# WT901.net
KiCad netlist of a schematic drawn in EAGLE
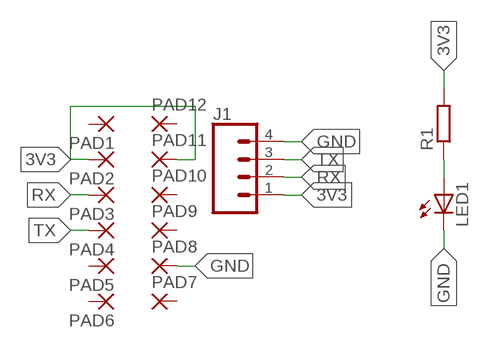
[diagram p0: schematic, sheet 1]

(export (version "E")
  (design (tool "Eeschema 10.0.6"))
  (components
    (comp (ref "J1")
      (value "CONN_04JST-SMD")
      (footprint "eagle-import:JST-4-SMD")
      (libsource (lib "eagle-import") (part "CONN_04JST-SMD"))
    )
    (comp (ref "LED1")
      (value "LEDCHIPLED_0805")
      (footprint "eagle-import:CHIPLED_0805")
      (libsource (lib "eagle-import") (part "LEDCHIPLED_0805"))
    )
    (comp (ref "PAD1")
      (value "SMD2")
      (footprint "eagle-import:SMD1,27-2,54")
      (libsource (lib "eagle-import") (part "SMD2"))
    )
    (comp (ref "PAD2")
      (value "SMD2")
      (footprint "eagle-import:SMD1,27-2,54")
      (libsource (lib "eagle-import") (part "SMD2"))
    )
    (comp (ref "PAD3")
      (value "SMD2")
      (footprint "eagle-import:SMD1,27-2,54")
      (libsource (lib "eagle-import") (part "SMD2"))
    )
    (comp (ref "PAD4")
      (value "SMD2")
      (footprint "eagle-import:SMD1,27-2,54")
      (libsource (lib "eagle-import") (part "SMD2"))
    )
    (comp (ref "PAD5")
      (value "SMD2")
      (footprint "eagle-import:SMD1,27-2,54")
      (libsource (lib "eagle-import") (part "SMD2"))
    )
    (comp (ref "PAD6")
      (value "SMD2")
      (footprint "eagle-import:SMD1,27-2,54")
      (libsource (lib "eagle-import") (part "SMD2"))
    )
    (comp (ref "PAD7")
      (value "SMD2")
      (footprint "eagle-import:SMD1,27-2,54")
      (libsource (lib "eagle-import") (part "SMD2"))
    )
    (comp (ref "PAD8")
      (value "SMD2")
      (footprint "eagle-import:SMD1,27-2,54")
      (libsource (lib "eagle-import") (part "SMD2"))
    )
    (comp (ref "PAD9")
      (value "SMD2")
      (footprint "eagle-import:SMD1,27-2,54")
      (libsource (lib "eagle-import") (part "SMD2"))
    )
    (comp (ref "PAD10")
      (value "SMD2")
      (footprint "eagle-import:SMD1,27-2,54")
      (libsource (lib "eagle-import") (part "SMD2"))
    )
    (comp (ref "PAD11")
      (value "SMD2")
      (footprint "eagle-import:SMD1,27-2,54")
      (libsource (lib "eagle-import") (part "SMD2"))
    )
    (comp (ref "PAD12")
      (value "SMD2")
      (footprint "eagle-import:SMD1,27-2,54")
      (libsource (lib "eagle-import") (part "SMD2"))
    )
    (comp (ref "R1")
      (value "R-EU_R0805")
      (footprint "eagle-import:R0805")
      (libsource (lib "eagle-import") (part "R-EU_R0805"))
    )
  )
  (nets
    (net (code "1") (name "3V3") (class "Default")
      (node (ref "J1") (pin "1") (pinfunction "1_1") (pintype "passive"))
      (node (ref "PAD11") (pin "1") (pinfunction "P_1") (pintype "passive"))
      (node (ref "PAD2") (pin "1") (pinfunction "P_1") (pintype "passive"))
      (node (ref "R1") (pin "2") (pinfunction "2_2") (pintype "passive"))
    )
    (net (code "2") (name "GND") (class "Default")
      (node (ref "J1") (pin "4") (pinfunction "4_4") (pintype "passive"))
      (node (ref "LED1") (pin "C") (pinfunction "C_C") (pintype "passive"))
      (node (ref "PAD8") (pin "1") (pinfunction "P_1") (pintype "passive"))
    )
    (net (code "3") (name "Net-(LED1-PadA)") (class "Default")
      (node (ref "LED1") (pin "A") (pinfunction "A_A") (pintype "passive"))
      (node (ref "R1") (pin "1") (pinfunction "1_1") (pintype "passive"))
    )
    (net (code "4") (name "RX") (class "Default")
      (node (ref "J1") (pin "2") (pinfunction "2_2") (pintype "passive"))
      (node (ref "PAD3") (pin "1") (pinfunction "P_1") (pintype "passive"))
    )
    (net (code "5") (name "TX") (class "Default")
      (node (ref "J1") (pin "3") (pinfunction "3_3") (pintype "passive"))
      (node (ref "PAD4") (pin "1") (pinfunction "P_1") (pintype "passive"))
    )
    (net (code "6") (name "unconnected-(PAD1-P-Pad1)") (class "Default")
      (node (ref "PAD1") (pin "1") (pinfunction "P_1") (pintype "passive"))
    )
    (net (code "7") (name "unconnected-(PAD5-P-Pad1)") (class "Default")
      (node (ref "PAD5") (pin "1") (pinfunction "P_1") (pintype "passive"))
    )
    (net (code "8") (name "unconnected-(PAD6-P-Pad1)") (class "Default")
      (node (ref "PAD6") (pin "1") (pinfunction "P_1") (pintype "passive"))
    )
    (net (code "9") (name "unconnected-(PAD7-P-Pad1)") (class "Default")
      (node (ref "PAD7") (pin "1") (pinfunction "P_1") (pintype "passive"))
    )
    (net (code "10") (name "unconnected-(PAD9-P-Pad1)") (class "Default")
      (node (ref "PAD9") (pin "1") (pinfunction "P_1") (pintype "passive"))
    )
    (net (code "11") (name "unconnected-(PAD10-P-Pad1)") (class "Default")
      (node (ref "PAD10") (pin "1") (pinfunction "P_1") (pintype "passive"))
    )
    (net (code "12") (name "unconnected-(PAD12-P-Pad1)") (class "Default")
      (node (ref "PAD12") (pin "1") (pinfunction "P_1") (pintype "passive"))
    )
  )
)
